# matrix.net
KiCad netlist of a schematic drawn in Altium Designer
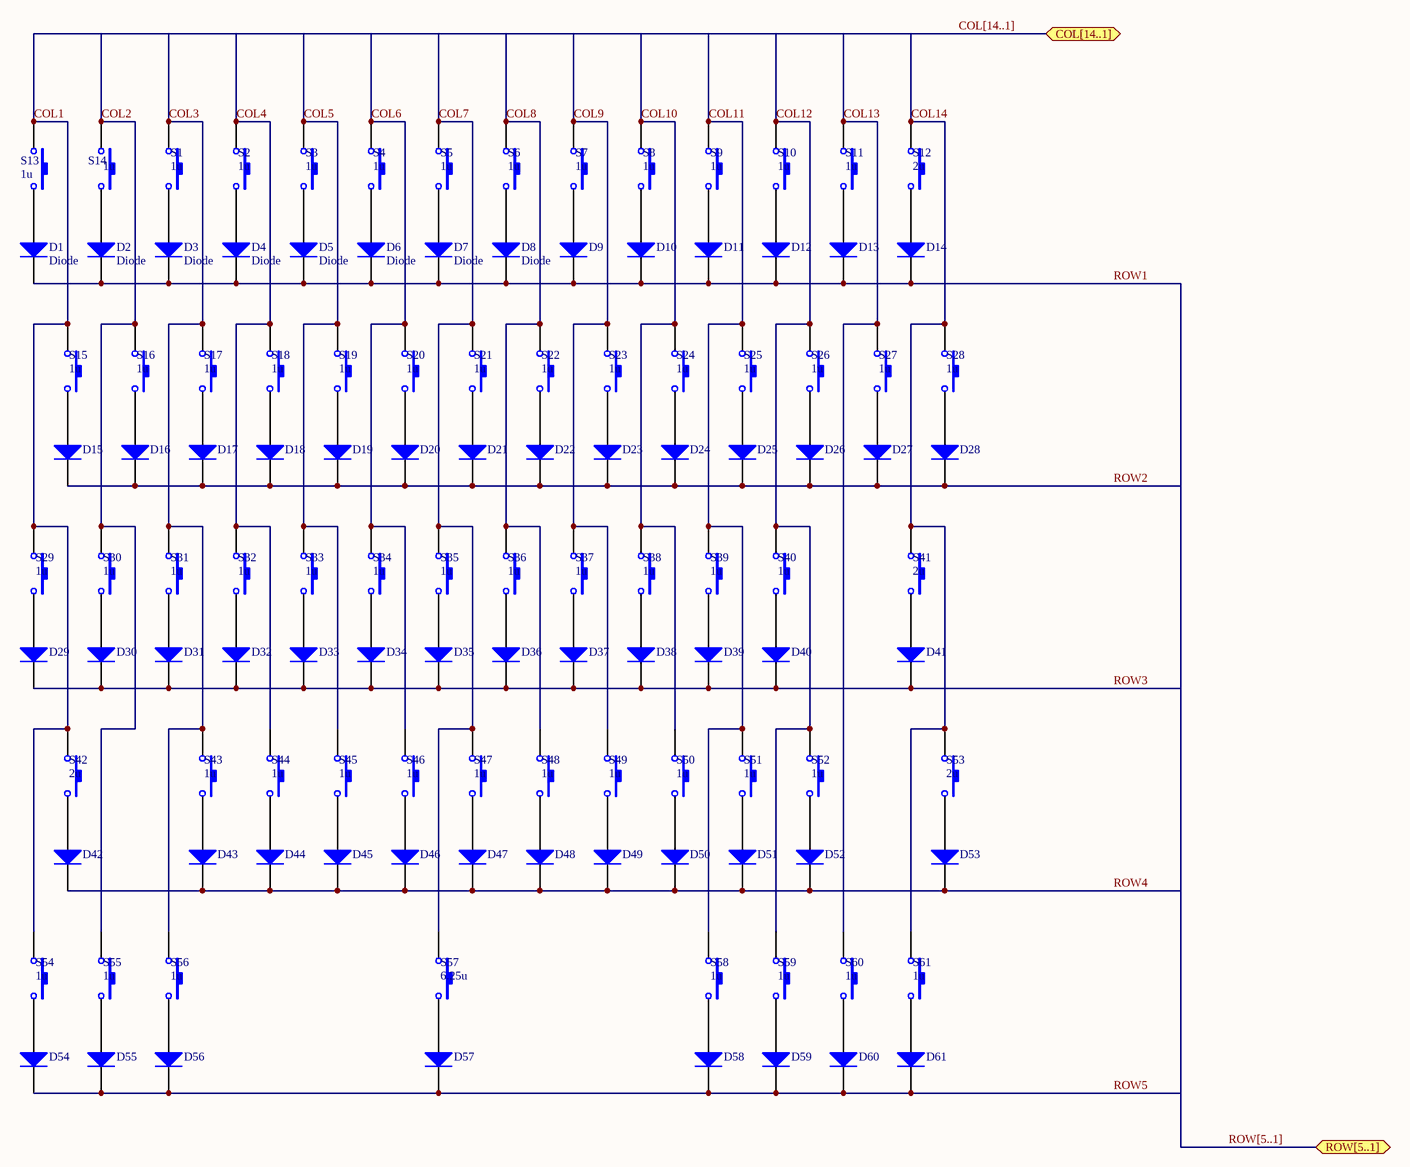
[diagram p0: matrix.SchDoc]

(export (version "E")
  (design (tool "Eeschema 10.0.6"))
  (components
    (comp (ref "D1") (value "Diode") (footprint "SOD-323f") (libsource (lib "MKNZ") (part "Diode")))
    (comp (ref "D2") (value "Diode") (footprint "SOD-323f") (libsource (lib "MKNZ") (part "Diode")))
    (comp (ref "D3") (value "Diode") (footprint "SOD-323f") (libsource (lib "MKNZ") (part "Diode")))
    (comp (ref "D4") (value "Diode") (footprint "SOD-323f") (libsource (lib "MKNZ") (part "Diode")))
    (comp (ref "D5") (value "Diode") (footprint "SOD-323f") (libsource (lib "MKNZ") (part "Diode")))
    (comp (ref "D6") (value "Diode") (footprint "SOD-323f") (libsource (lib "MKNZ") (part "Diode")))
    (comp (ref "D7") (value "Diode") (footprint "SOD-323f") (libsource (lib "MKNZ") (part "Diode")))
    (comp (ref "D8") (value "Diode") (footprint "SOD-323f") (libsource (lib "MKNZ") (part "Diode")))
    (comp (ref "D9") (value "Diode") (footprint "SOD-323f") (libsource (lib "MKNZ") (part "Diode")))
    (comp (ref "D10") (value "Diode") (footprint "SOD-323f") (libsource (lib "MKNZ") (part "Diode")))
    (comp (ref "D11") (value "Diode") (footprint "SOD-323f") (libsource (lib "MKNZ") (part "Diode")))
    (comp (ref "D12") (value "Diode") (footprint "SOD-323f") (libsource (lib "MKNZ") (part "Diode")))
    (comp (ref "D13") (value "Diode") (footprint "SOD-323f") (libsource (lib "MKNZ") (part "Diode")))
    (comp (ref "D14") (value "Diode") (footprint "SOD-323f") (libsource (lib "MKNZ") (part "Diode")))
    (comp (ref "D15") (value "Diode") (footprint "SOD-323f") (libsource (lib "MKNZ") (part "Diode")))
    (comp (ref "D16") (value "Diode") (footprint "SOD-323f") (libsource (lib "MKNZ") (part "Diode")))
    (comp (ref "D17") (value "Diode") (footprint "SOD-323f") (libsource (lib "MKNZ") (part "Diode")))
    (comp (ref "D18") (value "Diode") (footprint "SOD-323f") (libsource (lib "MKNZ") (part "Diode")))
    (comp (ref "D19") (value "Diode") (footprint "SOD-323f") (libsource (lib "MKNZ") (part "Diode")))
    (comp (ref "D20") (value "Diode") (footprint "SOD-323f") (libsource (lib "MKNZ") (part "Diode")))
    (comp (ref "D21") (value "Diode") (footprint "SOD-323f") (libsource (lib "MKNZ") (part "Diode")))
    (comp (ref "D22") (value "Diode") (footprint "SOD-323f") (libsource (lib "MKNZ") (part "Diode")))
    (comp (ref "D23") (value "Diode") (footprint "SOD-323f") (libsource (lib "MKNZ") (part "Diode")))
    (comp (ref "D24") (value "Diode") (footprint "SOD-323f") (libsource (lib "MKNZ") (part "Diode")))
    (comp (ref "D25") (value "Diode") (footprint "SOD-323f") (libsource (lib "MKNZ") (part "Diode")))
    (comp (ref "D26") (value "Diode") (footprint "SOD-323f") (libsource (lib "MKNZ") (part "Diode")))
    (comp (ref "D27") (value "Diode") (footprint "SOD-323f") (libsource (lib "MKNZ") (part "Diode")))
    (comp (ref "D28") (value "Diode") (footprint "SOD-323f") (libsource (lib "MKNZ") (part "Diode")))
    (comp (ref "D29") (value "Diode") (footprint "SOD-323f") (libsource (lib "MKNZ") (part "Diode")))
    (comp (ref "D30") (value "Diode") (footprint "SOD-323f") (libsource (lib "MKNZ") (part "Diode")))
    (comp (ref "D31") (value "Diode") (footprint "SOD-323f") (libsource (lib "MKNZ") (part "Diode")))
    (comp (ref "D32") (value "Diode") (footprint "SOD-323f") (libsource (lib "MKNZ") (part "Diode")))
    (comp (ref "D33") (value "Diode") (footprint "SOD-323f") (libsource (lib "MKNZ") (part "Diode")))
    (comp (ref "D34") (value "Diode") (footprint "SOD-323f") (libsource (lib "MKNZ") (part "Diode")))
    (comp (ref "D35") (value "Diode") (footprint "SOD-323f") (libsource (lib "MKNZ") (part "Diode")))
    (comp (ref "D36") (value "Diode") (footprint "SOD-323f") (libsource (lib "MKNZ") (part "Diode")))
    (comp (ref "D37") (value "Diode") (footprint "SOD-323f") (libsource (lib "MKNZ") (part "Diode")))
    (comp (ref "D38") (value "Diode") (footprint "SOD-323f") (libsource (lib "MKNZ") (part "Diode")))
    (comp (ref "D39") (value "Diode") (footprint "SOD-323f") (libsource (lib "MKNZ") (part "Diode")))
    (comp (ref "D40") (value "Diode") (footprint "SOD-323f") (libsource (lib "MKNZ") (part "Diode")))
    (comp (ref "D41") (value "Diode") (footprint "SOD-323f") (libsource (lib "MKNZ") (part "Diode")))
    (comp (ref "D42") (value "Diode") (footprint "SOD-323f") (libsource (lib "MKNZ") (part "Diode")))
    (comp (ref "D43") (value "Diode") (footprint "SOD-323f") (libsource (lib "MKNZ") (part "Diode")))
    (comp (ref "D44") (value "Diode") (footprint "SOD-323f") (libsource (lib "MKNZ") (part "Diode")))
    (comp (ref "D45") (value "Diode") (footprint "SOD-323f") (libsource (lib "MKNZ") (part "Diode")))
    (comp (ref "D46") (value "Diode") (footprint "SOD-323f") (libsource (lib "MKNZ") (part "Diode")))
    (comp (ref "D47") (value "Diode") (footprint "SOD-323f") (libsource (lib "MKNZ") (part "Diode")))
    (comp (ref "D48") (value "Diode") (footprint "SOD-323f") (libsource (lib "MKNZ") (part "Diode")))
    (comp (ref "D49") (value "Diode") (footprint "SOD-323f") (libsource (lib "MKNZ") (part "Diode")))
    (comp (ref "D50") (value "Diode") (footprint "SOD-323f") (libsource (lib "MKNZ") (part "Diode")))
    (comp (ref "D51") (value "Diode") (footprint "SOD-323f") (libsource (lib "MKNZ") (part "Diode")))
    (comp (ref "D52") (value "Diode") (footprint "SOD-323f") (libsource (lib "MKNZ") (part "Diode")))
    (comp (ref "D53") (value "Diode") (footprint "SOD-323f") (libsource (lib "MKNZ") (part "Diode")))
    (comp (ref "D54") (value "Diode") (footprint "SOD-323f") (libsource (lib "MKNZ") (part "Diode")))
    (comp (ref "D55") (value "Diode") (footprint "SOD-323f") (libsource (lib "MKNZ") (part "Diode")))
    (comp (ref "D56") (value "Diode") (footprint "SOD-323f") (libsource (lib "MKNZ") (part "Diode")))
    (comp (ref "D57") (value "Diode") (footprint "SOD-323f") (libsource (lib "MKNZ") (part "Diode")))
    (comp (ref "D58") (value "Diode") (footprint "SOD-323f") (libsource (lib "MKNZ") (part "Diode")))
    (comp (ref "D59") (value "Diode") (footprint "SOD-323f") (libsource (lib "MKNZ") (part "Diode")))
    (comp (ref "D60") (value "Diode") (footprint "SOD-323f") (libsource (lib "MKNZ") (part "Diode")))
    (comp (ref "D61") (value "Diode") (footprint "SOD-323f") (libsource (lib "MKNZ") (part "Diode")))
    (comp (ref "S1")
      (value "1u")
      (footprint "mx1u")
      (description "1-2u Mx Switch")
      (libsource (lib "MKNZ") (part "1u"))
    )
    (comp (ref "S2")
      (value "1u")
      (footprint "mx1u")
      (description "1-2u Mx Switch")
      (libsource (lib "MKNZ") (part "1u"))
    )
    (comp (ref "S3")
      (value "1u")
      (footprint "mx1u")
      (description "1-2u Mx Switch")
      (libsource (lib "MKNZ") (part "1u"))
    )
    (comp (ref "S4")
      (value "1u")
      (footprint "mx1u")
      (description "1-2u Mx Switch")
      (libsource (lib "MKNZ") (part "1u"))
    )
    (comp (ref "S5")
      (value "1u")
      (footprint "mx1u")
      (description "1-2u Mx Switch")
      (libsource (lib "MKNZ") (part "1u"))
    )
    (comp (ref "S6")
      (value "1u")
      (footprint "mx1u")
      (description "1-2u Mx Switch")
      (libsource (lib "MKNZ") (part "1u"))
    )
    (comp (ref "S7")
      (value "1u")
      (footprint "mx1u")
      (description "1-2u Mx Switch")
      (libsource (lib "MKNZ") (part "1u"))
    )
    (comp (ref "S8")
      (value "1u")
      (footprint "mx1u")
      (description "1-2u Mx Switch")
      (libsource (lib "MKNZ") (part "1u"))
    )
    (comp (ref "S9")
      (value "1u")
      (footprint "mx1u")
      (description "1-2u Mx Switch")
      (libsource (lib "MKNZ") (part "1u"))
    )
    (comp (ref "S10")
      (value "1u")
      (footprint "mx1u")
      (description "1-2u Mx Switch")
      (libsource (lib "MKNZ") (part "1u"))
    )
    (comp (ref "S11")
      (value "1u")
      (footprint "mx1u")
      (description "1-2u Mx Switch")
      (libsource (lib "MKNZ") (part "1u"))
    )
    (comp (ref "S12")
      (value "2u")
      (footprint "mx2u")
      (description "2-3u Mx Switch with pcb mount stabs")
      (libsource (lib "MKNZ") (part "2u"))
    )
    (comp (ref "S13")
      (value "1u")
      (footprint "mx1u")
      (description "1-2u Mx Switch")
      (libsource (lib "MKNZ") (part "1u"))
    )
    (comp (ref "S14")
      (value "1u")
      (footprint "mx1u")
      (description "1-2u Mx Switch")
      (libsource (lib "MKNZ") (part "1u"))
    )
    (comp (ref "S15")
      (value "1u")
      (footprint "mx1u")
      (description "1-2u Mx Switch")
      (libsource (lib "MKNZ") (part "1u"))
    )
    (comp (ref "S16")
      (value "1u")
      (footprint "mx1u")
      (description "1-2u Mx Switch")
      (libsource (lib "MKNZ") (part "1u"))
    )
    (comp (ref "S17")
      (value "1u")
      (footprint "mx1u")
      (description "1-2u Mx Switch")
      (libsource (lib "MKNZ") (part "1u"))
    )
    (comp (ref "S18")
      (value "1u")
      (footprint "mx1u")
      (description "1-2u Mx Switch")
      (libsource (lib "MKNZ") (part "1u"))
    )
    (comp (ref "S19")
      (value "1u")
      (footprint "mx1u")
      (description "1-2u Mx Switch")
      (libsource (lib "MKNZ") (part "1u"))
    )
    (comp (ref "S20")
      (value "1u")
      (footprint "mx1u")
      (description "1-2u Mx Switch")
      (libsource (lib "MKNZ") (part "1u"))
    )
    (comp (ref "S21")
      (value "1u")
      (footprint "mx1u")
      (description "1-2u Mx Switch")
      (libsource (lib "MKNZ") (part "1u"))
    )
    (comp (ref "S22")
      (value "1u")
      (footprint "mx1u")
      (description "1-2u Mx Switch")
      (libsource (lib "MKNZ") (part "1u"))
    )
    (comp (ref "S23")
      (value "1u")
      (footprint "mx1u")
      (description "1-2u Mx Switch")
      (libsource (lib "MKNZ") (part "1u"))
    )
    (comp (ref "S24")
      (value "1u")
      (footprint "mx1u")
      (description "1-2u Mx Switch")
      (libsource (lib "MKNZ") (part "1u"))
    )
    (comp (ref "S25")
      (value "1u")
      (footprint "mx1u")
      (description "1-2u Mx Switch")
      (libsource (lib "MKNZ") (part "1u"))
    )
    (comp (ref "S26")
      (value "1u")
      (footprint "mx1u")
      (description "1-2u Mx Switch")
      (libsource (lib "MKNZ") (part "1u"))
    )
    (comp (ref "S27")
      (value "1u")
      (footprint "mx1u")
      (description "1-2u Mx Switch")
      (libsource (lib "MKNZ") (part "1u"))
    )
    (comp (ref "S28")
      (value "1u")
      (footprint "mx1u")
      (description "1-2u Mx Switch")
      (libsource (lib "MKNZ") (part "1u"))
    )
    (comp (ref "S29")
      (value "1u")
      (footprint "mx1u")
      (description "1-2u Mx Switch")
      (libsource (lib "MKNZ") (part "1u"))
    )
    (comp (ref "S30")
      (value "1u")
      (footprint "mx1u")
      (description "1-2u Mx Switch")
      (libsource (lib "MKNZ") (part "1u"))
    )
    (comp (ref "S31")
      (value "1u")
      (footprint "mx1u")
      (description "1-2u Mx Switch")
      (libsource (lib "MKNZ") (part "1u"))
    )
    (comp (ref "S32")
      (value "1u")
      (footprint "mx1u")
      (description "1-2u Mx Switch")
      (libsource (lib "MKNZ") (part "1u"))
    )
    (comp (ref "S33")
      (value "1u")
      (footprint "mx1u")
      (description "1-2u Mx Switch")
      (libsource (lib "MKNZ") (part "1u"))
    )
    (comp (ref "S34")
      (value "1u")
      (footprint "mx1u")
      (description "1-2u Mx Switch")
      (libsource (lib "MKNZ") (part "1u"))
    )
    (comp (ref "S35")
      (value "1u")
      (footprint "mx1u")
      (description "1-2u Mx Switch")
      (libsource (lib "MKNZ") (part "1u"))
    )
    (comp (ref "S36")
      (value "1u")
      (footprint "mx1u")
      (description "1-2u Mx Switch")
      (libsource (lib "MKNZ") (part "1u"))
    )
    (comp (ref "S37")
      (value "1u")
      (footprint "mx1u")
      (description "1-2u Mx Switch")
      (libsource (lib "MKNZ") (part "1u"))
    )
    (comp (ref "S38")
      (value "1u")
      (footprint "mx1u")
      (description "1-2u Mx Switch")
      (libsource (lib "MKNZ") (part "1u"))
    )
    (comp (ref "S39")
      (value "1u")
      (footprint "mx1u")
      (description "1-2u Mx Switch")
      (libsource (lib "MKNZ") (part "1u"))
    )
    (comp (ref "S40")
      (value "1u")
      (footprint "mx1u")
      (description "1-2u Mx Switch")
      (libsource (lib "MKNZ") (part "1u"))
    )
    (comp (ref "S41")
      (value "2u")
      (footprint "mx2u")
      (description "2-3u Mx Switch with pcb mount stabs")
      (libsource (lib "MKNZ") (part "2u"))
    )
    (comp (ref "S42")
      (value "2u")
      (footprint "mx2u")
      (description "2-3u Mx Switch with pcb mount stabs")
      (libsource (lib "MKNZ") (part "2u"))
    )
    (comp (ref "S43")
      (value "1u")
      (footprint "mx1u")
      (description "1-2u Mx Switch")
      (libsource (lib "MKNZ") (part "1u"))
    )
    (comp (ref "S44")
      (value "1u")
      (footprint "mx1u")
      (description "1-2u Mx Switch")
      (libsource (lib "MKNZ") (part "1u"))
    )
    (comp (ref "S45")
      (value "1u")
      (footprint "mx1u")
      (description "1-2u Mx Switch")
      (libsource (lib "MKNZ") (part "1u"))
    )
    (comp (ref "S46")
      (value "1u")
      (footprint "mx1u")
      (description "1-2u Mx Switch")
      (libsource (lib "MKNZ") (part "1u"))
    )
    (comp (ref "S47")
      (value "1u")
      (footprint "mx1u")
      (description "1-2u Mx Switch")
      (libsource (lib "MKNZ") (part "1u"))
    )
    (comp (ref "S48")
      (value "1u")
      (footprint "mx1u")
      (description "1-2u Mx Switch")
      (libsource (lib "MKNZ") (part "1u"))
    )
    (comp (ref "S49")
      (value "1u")
      (footprint "mx1u")
      (description "1-2u Mx Switch")
      (libsource (lib "MKNZ") (part "1u"))
    )
    (comp (ref "S50")
      (value "1u")
      (footprint "mx1u")
      (description "1-2u Mx Switch")
      (libsource (lib "MKNZ") (part "1u"))
    )
    (comp (ref "S51")
      (value "1u")
      (footprint "mx1u")
      (description "1-2u Mx Switch")
      (libsource (lib "MKNZ") (part "1u"))
    )
    (comp (ref "S52")
      (value "1u")
      (footprint "mx1u")
      (description "1-2u Mx Switch")
      (libsource (lib "MKNZ") (part "1u"))
    )
    (comp (ref "S53")
      (value "2u")
      (footprint "mx2u")
      (description "2-3u Mx Switch with pcb mount stabs")
      (libsource (lib "MKNZ") (part "2u"))
    )
    (comp (ref "S54")
      (value "1u")
      (footprint "mx1u")
      (description "1-2u Mx Switch")
      (libsource (lib "MKNZ") (part "1u"))
    )
    (comp (ref "S55")
      (value "1u")
      (footprint "mx1u")
      (description "1-2u Mx Switch")
      (libsource (lib "MKNZ") (part "1u"))
    )
    (comp (ref "S56")
      (value "1u")
      (footprint "mx1u")
      (description "1-2u Mx Switch")
      (libsource (lib "MKNZ") (part "1u"))
    )
    (comp (ref "S57")
      (value "6.25u")
      (footprint "mx6.25u flipped stab")
      (description "6.25u Mx Switch with pcb mount stabs")
      (libsource (lib "MKNZ") (part "6.25u"))
    )
    (comp (ref "S58")
      (value "1u")
      (footprint "mx1u")
      (description "1-2u Mx Switch")
      (libsource (lib "MKNZ") (part "1u"))
    )
    (comp (ref "S59")
      (value "1u")
      (footprint "mx1u")
      (description "1-2u Mx Switch")
      (libsource (lib "MKNZ") (part "1u"))
    )
    (comp (ref "S60")
      (value "1u")
      (footprint "mx1u")
      (description "1-2u Mx Switch")
      (libsource (lib "MKNZ") (part "1u"))
    )
    (comp (ref "S61")
      (value "1u")
      (footprint "mx1u")
      (description "1-2u Mx Switch")
      (libsource (lib "MKNZ") (part "1u"))
    )
  )
  (nets
    (net (code "1") (name "/COL1") (class "Default")
      (node (ref "S13") (pin "1") (pinfunction "1_1") (pintype "passive"))
      (node (ref "S15") (pin "1") (pinfunction "1_1") (pintype "passive"))
      (node (ref "S29") (pin "1") (pinfunction "1_1") (pintype "passive"))
      (node (ref "S42") (pin "1") (pinfunction "1_1") (pintype "passive"))
      (node (ref "S54") (pin "1") (pinfunction "1_1") (pintype "passive"))
    )
    (net (code "2") (name "/COL2") (class "Default")
      (node (ref "S14") (pin "1") (pinfunction "1_1") (pintype "passive"))
      (node (ref "S16") (pin "1") (pinfunction "1_1") (pintype "passive"))
      (node (ref "S30") (pin "1") (pinfunction "1_1") (pintype "passive"))
      (node (ref "S55") (pin "1") (pinfunction "1_1") (pintype "passive"))
    )
    (net (code "3") (name "/COL3") (class "Default")
      (node (ref "S1") (pin "1") (pinfunction "1_1") (pintype "passive"))
      (node (ref "S17") (pin "1") (pinfunction "1_1") (pintype "passive"))
      (node (ref "S31") (pin "1") (pinfunction "1_1") (pintype "passive"))
      (node (ref "S43") (pin "1") (pinfunction "1_1") (pintype "passive"))
      (node (ref "S56") (pin "1") (pinfunction "1_1") (pintype "passive"))
    )
    (net (code "4") (name "/COL4") (class "Default")
      (node (ref "S18") (pin "1") (pinfunction "1_1") (pintype "passive"))
      (node (ref "S2") (pin "1") (pinfunction "1_1") (pintype "passive"))
      (node (ref "S32") (pin "1") (pinfunction "1_1") (pintype "passive"))
      (node (ref "S44") (pin "1") (pinfunction "1_1") (pintype "passive"))
    )
    (net (code "5") (name "/COL5") (class "Default")
      (node (ref "S19") (pin "1") (pinfunction "1_1") (pintype "passive"))
      (node (ref "S3") (pin "1") (pinfunction "1_1") (pintype "passive"))
      (node (ref "S33") (pin "1") (pinfunction "1_1") (pintype "passive"))
      (node (ref "S45") (pin "1") (pinfunction "1_1") (pintype "passive"))
    )
    (net (code "6") (name "/COL6") (class "Default")
      (node (ref "S20") (pin "1") (pinfunction "1_1") (pintype "passive"))
      (node (ref "S34") (pin "1") (pinfunction "1_1") (pintype "passive"))
      (node (ref "S4") (pin "1") (pinfunction "1_1") (pintype "passive"))
      (node (ref "S46") (pin "1") (pinfunction "1_1") (pintype "passive"))
    )
    (net (code "7") (name "/COL7") (class "Default")
      (node (ref "S21") (pin "1") (pinfunction "1_1") (pintype "passive"))
      (node (ref "S35") (pin "1") (pinfunction "1_1") (pintype "passive"))
      (node (ref "S47") (pin "1") (pinfunction "1_1") (pintype "passive"))
      (node (ref "S5") (pin "1") (pinfunction "1_1") (pintype "passive"))
      (node (ref "S57") (pin "1") (pinfunction "1_1") (pintype "passive"))
    )
    (net (code "8") (name "/COL8") (class "Default")
      (node (ref "S22") (pin "1") (pinfunction "1_1") (pintype "passive"))
      (node (ref "S36") (pin "1") (pinfunction "1_1") (pintype "passive"))
      (node (ref "S48") (pin "1") (pinfunction "1_1") (pintype "passive"))
      (node (ref "S6") (pin "1") (pinfunction "1_1") (pintype "passive"))
    )
    (net (code "9") (name "/COL9") (class "Default")
      (node (ref "S23") (pin "1") (pinfunction "1_1") (pintype "passive"))
      (node (ref "S37") (pin "1") (pinfunction "1_1") (pintype "passive"))
      (node (ref "S49") (pin "1") (pinfunction "1_1") (pintype "passive"))
      (node (ref "S7") (pin "1") (pinfunction "1_1") (pintype "passive"))
    )
    (net (code "10") (name "/COL10") (class "Default")
      (node (ref "S24") (pin "1") (pinfunction "1_1") (pintype "passive"))
      (node (ref "S38") (pin "1") (pinfunction "1_1") (pintype "passive"))
      (node (ref "S50") (pin "1") (pinfunction "1_1") (pintype "passive"))
      (node (ref "S8") (pin "1") (pinfunction "1_1") (pintype "passive"))
    )
    (net (code "11") (name "/COL11") (class "Default")
      (node (ref "S25") (pin "1") (pinfunction "1_1") (pintype "passive"))
      (node (ref "S39") (pin "1") (pinfunction "1_1") (pintype "passive"))
      (node (ref "S51") (pin "1") (pinfunction "1_1") (pintype "passive"))
      (node (ref "S58") (pin "1") (pinfunction "1_1") (pintype "passive"))
      (node (ref "S9") (pin "1") (pinfunction "1_1") (pintype "passive"))
    )
    (net (code "12") (name "/COL12") (class "Default")
      (node (ref "S10") (pin "1") (pinfunction "1_1") (pintype "passive"))
      (node (ref "S26") (pin "1") (pinfunction "1_1") (pintype "passive"))
      (node (ref "S40") (pin "1") (pinfunction "1_1") (pintype "passive"))
      (node (ref "S52") (pin "1") (pinfunction "1_1") (pintype "passive"))
      (node (ref "S59") (pin "1") (pinfunction "1_1") (pintype "passive"))
    )
    (net (code "13") (name "/COL13") (class "Default")
      (node (ref "S11") (pin "1") (pinfunction "1_1") (pintype "passive"))
      (node (ref "S27") (pin "1") (pinfunction "1_1") (pintype "passive"))
      (node (ref "S60") (pin "1") (pinfunction "1_1") (pintype "passive"))
    )
    (net (code "14") (name "/COL14") (class "Default")
      (node (ref "S12") (pin "1") (pinfunction "1_1") (pintype "passive"))
      (node (ref "S28") (pin "1") (pinfunction "1_1") (pintype "passive"))
      (node (ref "S41") (pin "1") (pinfunction "1_1") (pintype "passive"))
      (node (ref "S53") (pin "1") (pinfunction "1_1") (pintype "passive"))
      (node (ref "S61") (pin "1") (pinfunction "1_1") (pintype "passive"))
    )
    (net (code "16") (name "/ROW1") (class "Default")
      (node (ref "D1") (pin "1") (pinfunction "K_1") (pintype "passive"))
      (node (ref "D10") (pin "1") (pinfunction "K_1") (pintype "passive"))
      (node (ref "D11") (pin "1") (pinfunction "K_1") (pintype "passive"))
      (node (ref "D12") (pin "1") (pinfunction "K_1") (pintype "passive"))
      (node (ref "D13") (pin "1") (pinfunction "K_1") (pintype "passive"))
      (node (ref "D14") (pin "1") (pinfunction "K_1") (pintype "passive"))
      (node (ref "D2") (pin "1") (pinfunction "K_1") (pintype "passive"))
      (node (ref "D3") (pin "1") (pinfunction "K_1") (pintype "passive"))
      (node (ref "D4") (pin "1") (pinfunction "K_1") (pintype "passive"))
      (node (ref "D5") (pin "1") (pinfunction "K_1") (pintype "passive"))
      (node (ref "D6") (pin "1") (pinfunction "K_1") (pintype "passive"))
      (node (ref "D7") (pin "1") (pinfunction "K_1") (pintype "passive"))
      (node (ref "D8") (pin "1") (pinfunction "K_1") (pintype "passive"))
      (node (ref "D9") (pin "1") (pinfunction "K_1") (pintype "passive"))
    )
    (net (code "17") (name "/ROW2") (class "Default")
      (node (ref "D15") (pin "1") (pinfunction "K_1") (pintype "passive"))
      (node (ref "D16") (pin "1") (pinfunction "K_1") (pintype "passive"))
      (node (ref "D17") (pin "1") (pinfunction "K_1") (pintype "passive"))
      (node (ref "D18") (pin "1") (pinfunction "K_1") (pintype "passive"))
      (node (ref "D19") (pin "1") (pinfunction "K_1") (pintype "passive"))
      (node (ref "D20") (pin "1") (pinfunction "K_1") (pintype "passive"))
      (node (ref "D21") (pin "1") (pinfunction "K_1") (pintype "passive"))
      (node (ref "D22") (pin "1") (pinfunction "K_1") (pintype "passive"))
      (node (ref "D23") (pin "1") (pinfunction "K_1") (pintype "passive"))
      (node (ref "D24") (pin "1") (pinfunction "K_1") (pintype "passive"))
      (node (ref "D25") (pin "1") (pinfunction "K_1") (pintype "passive"))
      (node (ref "D26") (pin "1") (pinfunction "K_1") (pintype "passive"))
      (node (ref "D27") (pin "1") (pinfunction "K_1") (pintype "passive"))
      (node (ref "D28") (pin "1") (pinfunction "K_1") (pintype "passive"))
    )
    (net (code "18") (name "/ROW3") (class "Default")
      (node (ref "D29") (pin "1") (pinfunction "K_1") (pintype "passive"))
      (node (ref "D30") (pin "1") (pinfunction "K_1") (pintype "passive"))
      (node (ref "D31") (pin "1") (pinfunction "K_1") (pintype "passive"))
      (node (ref "D32") (pin "1") (pinfunction "K_1") (pintype "passive"))
      (node (ref "D33") (pin "1") (pinfunction "K_1") (pintype "passive"))
      (node (ref "D34") (pin "1") (pinfunction "K_1") (pintype "passive"))
      (node (ref "D35") (pin "1") (pinfunction "K_1") (pintype "passive"))
      (node (ref "D36") (pin "1") (pinfunction "K_1") (pintype "passive"))
      (node (ref "D37") (pin "1") (pinfunction "K_1") (pintype "passive"))
      (node (ref "D38") (pin "1") (pinfunction "K_1") (pintype "passive"))
      (node (ref "D39") (pin "1") (pinfunction "K_1") (pintype "passive"))
      (node (ref "D40") (pin "1") (pinfunction "K_1") (pintype "passive"))
      (node (ref "D41") (pin "1") (pinfunction "K_1") (pintype "passive"))
    )
    (net (code "19") (name "/ROW4") (class "Default")
      (node (ref "D42") (pin "1") (pinfunction "K_1") (pintype "passive"))
      (node (ref "D43") (pin "1") (pinfunction "K_1") (pintype "passive"))
      (node (ref "D44") (pin "1") (pinfunction "K_1") (pintype "passive"))
      (node (ref "D45") (pin "1") (pinfunction "K_1") (pintype "passive"))
      (node (ref "D46") (pin "1") (pinfunction "K_1") (pintype "passive"))
      (node (ref "D47") (pin "1") (pinfunction "K_1") (pintype "passive"))
      (node (ref "D48") (pin "1") (pinfunction "K_1") (pintype "passive"))
      (node (ref "D49") (pin "1") (pinfunction "K_1") (pintype "passive"))
      (node (ref "D50") (pin "1") (pinfunction "K_1") (pintype "passive"))
      (node (ref "D51") (pin "1") (pinfunction "K_1") (pintype "passive"))
      (node (ref "D52") (pin "1") (pinfunction "K_1") (pintype "passive"))
      (node (ref "D53") (pin "1") (pinfunction "K_1") (pintype "passive"))
    )
    (net (code "20") (name "/ROW5") (class "Default")
      (node (ref "D54") (pin "1") (pinfunction "K_1") (pintype "passive"))
      (node (ref "D55") (pin "1") (pinfunction "K_1") (pintype "passive"))
      (node (ref "D56") (pin "1") (pinfunction "K_1") (pintype "passive"))
      (node (ref "D57") (pin "1") (pinfunction "K_1") (pintype "passive"))
      (node (ref "D58") (pin "1") (pinfunction "K_1") (pintype "passive"))
      (node (ref "D59") (pin "1") (pinfunction "K_1") (pintype "passive"))
      (node (ref "D60") (pin "1") (pinfunction "K_1") (pintype "passive"))
      (node (ref "D61") (pin "1") (pinfunction "K_1") (pintype "passive"))
    )
    (net (code "22") (name "Net-(D1-A)") (class "Default")
      (node (ref "D1") (pin "2") (pinfunction "A_2") (pintype "passive"))
      (node (ref "S13") (pin "2") (pinfunction "2_2") (pintype "passive"))
    )
    (net (code "23") (name "Net-(D2-A)") (class "Default")
      (node (ref "D2") (pin "2") (pinfunction "A_2") (pintype "passive"))
      (node (ref "S14") (pin "2") (pinfunction "2_2") (pintype "passive"))
    )
    (net (code "24") (name "Net-(D3-A)") (class "Default")
      (node (ref "D3") (pin "2") (pinfunction "A_2") (pintype "passive"))
      (node (ref "S1") (pin "2") (pinfunction "2_2") (pintype "passive"))
    )
    (net (code "25") (name "Net-(D4-A)") (class "Default")
      (node (ref "D4") (pin "2") (pinfunction "A_2") (pintype "passive"))
      (node (ref "S2") (pin "2") (pinfunction "2_2") (pintype "passive"))
    )
    (net (code "26") (name "Net-(D5-A)") (class "Default")
      (node (ref "D5") (pin "2") (pinfunction "A_2") (pintype "passive"))
      (node (ref "S3") (pin "2") (pinfunction "2_2") (pintype "passive"))
    )
    (net (code "27") (name "Net-(D6-A)") (class "Default")
      (node (ref "D6") (pin "2") (pinfunction "A_2") (pintype "passive"))
      (node (ref "S4") (pin "2") (pinfunction "2_2") (pintype "passive"))
    )
    (net (code "28") (name "Net-(D7-A)") (class "Default")
      (node (ref "D7") (pin "2") (pinfunction "A_2") (pintype "passive"))
      (node (ref "S5") (pin "2") (pinfunction "2_2") (pintype "passive"))
    )
    (net (code "29") (name "Net-(D8-A)") (class "Default")
      (node (ref "D8") (pin "2") (pinfunction "A_2") (pintype "passive"))
      (node (ref "S6") (pin "2") (pinfunction "2_2") (pintype "passive"))
    )
    (net (code "30") (name "Net-(D9-A)") (class "Default")
      (node (ref "D9") (pin "2") (pinfunction "A_2") (pintype "passive"))
      (node (ref "S7") (pin "2") (pinfunction "2_2") (pintype "passive"))
    )
    (net (code "31") (name "Net-(D10-A)") (class "Default")
      (node (ref "D10") (pin "2") (pinfunction "A_2") (pintype "passive"))
      (node (ref "S8") (pin "2") (pinfunction "2_2") (pintype "passive"))
    )
    (net (code "32") (name "Net-(D11-A)") (class "Default")
      (node (ref "D11") (pin "2") (pinfunction "A_2") (pintype "passive"))
      (node (ref "S9") (pin "2") (pinfunction "2_2") (pintype "passive"))
    )
    (net (code "33") (name "Net-(D12-A)") (class "Default")
      (node (ref "D12") (pin "2") (pinfunction "A_2") (pintype "passive"))
      (node (ref "S10") (pin "2") (pinfunction "2_2") (pintype "passive"))
    )
    (net (code "34") (name "Net-(D13-A)") (class "Default")
      (node (ref "D13") (pin "2") (pinfunction "A_2") (pintype "passive"))
      (node (ref "S11") (pin "2") (pinfunction "2_2") (pintype "passive"))
    )
    (net (code "35") (name "Net-(D14-A)") (class "Default")
      (node (ref "D14") (pin "2") (pinfunction "A_2") (pintype "passive"))
      (node (ref "S12") (pin "2") (pinfunction "2_2") (pintype "passive"))
    )
    (net (code "36") (name "Net-(D15-A)") (class "Default")
      (node (ref "D15") (pin "2") (pinfunction "A_2") (pintype "passive"))
      (node (ref "S15") (pin "2") (pinfunction "2_2") (pintype "passive"))
    )
    (net (code "37") (name "Net-(D16-A)") (class "Default")
      (node (ref "D16") (pin "2") (pinfunction "A_2") (pintype "passive"))
      (node (ref "S16") (pin "2") (pinfunction "2_2") (pintype "passive"))
    )
    (net (code "38") (name "Net-(D17-A)") (class "Default")
      (node (ref "D17") (pin "2") (pinfunction "A_2") (pintype "passive"))
      (node (ref "S17") (pin "2") (pinfunction "2_2") (pintype "passive"))
    )
    (net (code "39") (name "Net-(D18-A)") (class "Default")
      (node (ref "D18") (pin "2") (pinfunction "A_2") (pintype "passive"))
      (node (ref "S18") (pin "2") (pinfunction "2_2") (pintype "passive"))
    )
    (net (code "40") (name "Net-(D19-A)") (class "Default")
      (node (ref "D19") (pin "2") (pinfunction "A_2") (pintype "passive"))
      (node (ref "S19") (pin "2") (pinfunction "2_2") (pintype "passive"))
    )
    (net (code "41") (name "Net-(D20-A)") (class "Default")
      (node (ref "D20") (pin "2") (pinfunction "A_2") (pintype "passive"))
      (node (ref "S20") (pin "2") (pinfunction "2_2") (pintype "passive"))
    )
    (net (code "42") (name "Net-(D21-A)") (class "Default")
      (node (ref "D21") (pin "2") (pinfunction "A_2") (pintype "passive"))
      (node (ref "S21") (pin "2") (pinfunction "2_2") (pintype "passive"))
    )
    (net (code "43") (name "Net-(D22-A)") (class "Default")
      (node (ref "D22") (pin "2") (pinfunction "A_2") (pintype "passive"))
      (node (ref "S22") (pin "2") (pinfunction "2_2") (pintype "passive"))
    )
    (net (code "44") (name "Net-(D23-A)") (class "Default")
      (node (ref "D23") (pin "2") (pinfunction "A_2") (pintype "passive"))
      (node (ref "S23") (pin "2") (pinfunction "2_2") (pintype "passive"))
    )
    (net (code "45") (name "Net-(D24-A)") (class "Default")
      (node (ref "D24") (pin "2") (pinfunction "A_2") (pintype "passive"))
      (node (ref "S24") (pin "2") (pinfunction "2_2") (pintype "passive"))
    )
    (net (code "46") (name "Net-(D25-A)") (class "Default")
      (node (ref "D25") (pin "2") (pinfunction "A_2") (pintype "passive"))
      (node (ref "S25") (pin "2") (pinfunction "2_2") (pintype "passive"))
    )
    (net (code "47") (name "Net-(D26-A)") (class "Default")
      (node (ref "D26") (pin "2") (pinfunction "A_2") (pintype "passive"))
      (node (ref "S26") (pin "2") (pinfunction "2_2") (pintype "passive"))
    )
    (net (code "48") (name "Net-(D27-A)") (class "Default")
      (node (ref "D27") (pin "2") (pinfunction "A_2") (pintype "passive"))
      (node (ref "S27") (pin "2") (pinfunction "2_2") (pintype "passive"))
    )
    (net (code "49") (name "Net-(D28-A)") (class "Default")
      (node (ref "D28") (pin "2") (pinfunction "A_2") (pintype "passive"))
      (node (ref "S28") (pin "2") (pinfunction "2_2") (pintype "passive"))
    )
    (net (code "50") (name "Net-(D29-A)") (class "Default")
      (node (ref "D29") (pin "2") (pinfunction "A_2") (pintype "passive"))
      (node (ref "S29") (pin "2") (pinfunction "2_2") (pintype "passive"))
    )
    (net (code "51") (name "Net-(D30-A)") (class "Default")
      (node (ref "D30") (pin "2") (pinfunction "A_2") (pintype "passive"))
      (node (ref "S30") (pin "2") (pinfunction "2_2") (pintype "passive"))
    )
    (net (code "52") (name "Net-(D31-A)") (class "Default")
      (node (ref "D31") (pin "2") (pinfunction "A_2") (pintype "passive"))
      (node (ref "S31") (pin "2") (pinfunction "2_2") (pintype "passive"))
    )
    (net (code "53") (name "Net-(D32-A)") (class "Default")
      (node (ref "D32") (pin "2") (pinfunction "A_2") (pintype "passive"))
      (node (ref "S32") (pin "2") (pinfunction "2_2") (pintype "passive"))
    )
    (net (code "54") (name "Net-(D33-A)") (class "Default")
      (node (ref "D33") (pin "2") (pinfunction "A_2") (pintype "passive"))
      (node (ref "S33") (pin "2") (pinfunction "2_2") (pintype "passive"))
    )
    (net (code "55") (name "Net-(D34-A)") (class "Default")
      (node (ref "D34") (pin "2") (pinfunction "A_2") (pintype "passive"))
      (node (ref "S34") (pin "2") (pinfunction "2_2") (pintype "passive"))
    )
    (net (code "56") (name "Net-(D35-A)") (class "Default")
      (node (ref "D35") (pin "2") (pinfunction "A_2") (pintype "passive"))
      (node (ref "S35") (pin "2") (pinfunction "2_2") (pintype "passive"))
    )
    (net (code "57") (name "Net-(D36-A)") (class "Default")
      (node (ref "D36") (pin "2") (pinfunction "A_2") (pintype "passive"))
      (node (ref "S36") (pin "2") (pinfunction "2_2") (pintype "passive"))
    )
    (net (code "58") (name "Net-(D37-A)") (class "Default")
      (node (ref "D37") (pin "2") (pinfunction "A_2") (pintype "passive"))
      (node (ref "S37") (pin "2") (pinfunction "2_2") (pintype "passive"))
    )
    (net (code "59") (name "Net-(D38-A)") (class "Default")
      (node (ref "D38") (pin "2") (pinfunction "A_2") (pintype "passive"))
      (node (ref "S38") (pin "2") (pinfunction "2_2") (pintype "passive"))
    )
    (net (code "60") (name "Net-(D39-A)") (class "Default")
      (node (ref "D39") (pin "2") (pinfunction "A_2") (pintype "passive"))
      (node (ref "S39") (pin "2") (pinfunction "2_2") (pintype "passive"))
    )
    (net (code "61") (name "Net-(D40-A)") (class "Default")
      (node (ref "D40") (pin "2") (pinfunction "A_2") (pintype "passive"))
      (node (ref "S40") (pin "2") (pinfunction "2_2") (pintype "passive"))
    )
    (net (code "62") (name "Net-(D41-A)") (class "Default")
      (node (ref "D41") (pin "2") (pinfunction "A_2") (pintype "passive"))
      (node (ref "S41") (pin "2") (pinfunction "2_2") (pintype "passive"))
    )
    (net (code "63") (name "Net-(D42-A)") (class "Default")
      (node (ref "D42") (pin "2") (pinfunction "A_2") (pintype "passive"))
      (node (ref "S42") (pin "2") (pinfunction "2_2") (pintype "passive"))
    )
    (net (code "64") (name "Net-(D43-A)") (class "Default")
      (node (ref "D43") (pin "2") (pinfunction "A_2") (pintype "passive"))
      (node (ref "S43") (pin "2") (pinfunction "2_2") (pintype "passive"))
    )
    (net (code "65") (name "Net-(D44-A)") (class "Default")
      (node (ref "D44") (pin "2") (pinfunction "A_2") (pintype "passive"))
      (node (ref "S44") (pin "2") (pinfunction "2_2") (pintype "passive"))
    )
    (net (code "66") (name "Net-(D45-A)") (class "Default")
      (node (ref "D45") (pin "2") (pinfunction "A_2") (pintype "passive"))
      (node (ref "S45") (pin "2") (pinfunction "2_2") (pintype "passive"))
    )
    (net (code "67") (name "Net-(D46-A)") (class "Default")
      (node (ref "D46") (pin "2") (pinfunction "A_2") (pintype "passive"))
      (node (ref "S46") (pin "2") (pinfunction "2_2") (pintype "passive"))
    )
    (net (code "68") (name "Net-(D47-A)") (class "Default")
      (node (ref "D47") (pin "2") (pinfunction "A_2") (pintype "passive"))
      (node (ref "S47") (pin "2") (pinfunction "2_2") (pintype "passive"))
    )
    (net (code "69") (name "Net-(D48-A)") (class "Default")
      (node (ref "D48") (pin "2") (pinfunction "A_2") (pintype "passive"))
      (node (ref "S48") (pin "2") (pinfunction "2_2") (pintype "passive"))
    )
    (net (code "70") (name "Net-(D49-A)") (class "Default")
      (node (ref "D49") (pin "2") (pinfunction "A_2") (pintype "passive"))
      (node (ref "S49") (pin "2") (pinfunction "2_2") (pintype "passive"))
    )
    (net (code "71") (name "Net-(D50-A)") (class "Default")
      (node (ref "D50") (pin "2") (pinfunction "A_2") (pintype "passive"))
      (node (ref "S50") (pin "2") (pinfunction "2_2") (pintype "passive"))
    )
    (net (code "72") (name "Net-(D51-A)") (class "Default")
      (node (ref "D51") (pin "2") (pinfunction "A_2") (pintype "passive"))
      (node (ref "S51") (pin "2") (pinfunction "2_2") (pintype "passive"))
    )
    (net (code "73") (name "Net-(D52-A)") (class "Default")
      (node (ref "D52") (pin "2") (pinfunction "A_2") (pintype "passive"))
      (node (ref "S52") (pin "2") (pinfunction "2_2") (pintype "passive"))
    )
    (net (code "74") (name "Net-(D53-A)") (class "Default")
      (node (ref "D53") (pin "2") (pinfunction "A_2") (pintype "passive"))
      (node (ref "S53") (pin "2") (pinfunction "2_2") (pintype "passive"))
    )
    (net (code "75") (name "Net-(D54-A)") (class "Default")
      (node (ref "D54") (pin "2") (pinfunction "A_2") (pintype "passive"))
      (node (ref "S54") (pin "2") (pinfunction "2_2") (pintype "passive"))
    )
    (net (code "76") (name "Net-(D55-A)") (class "Default")
      (node (ref "D55") (pin "2") (pinfunction "A_2") (pintype "passive"))
      (node (ref "S55") (pin "2") (pinfunction "2_2") (pintype "passive"))
    )
    (net (code "77") (name "Net-(D56-A)") (class "Default")
      (node (ref "D56") (pin "2") (pinfunction "A_2") (pintype "passive"))
      (node (ref "S56") (pin "2") (pinfunction "2_2") (pintype "passive"))
    )
    (net (code "78") (name "Net-(D57-A)") (class "Default")
      (node (ref "D57") (pin "2") (pinfunction "A_2") (pintype "passive"))
      (node (ref "S57") (pin "2") (pinfunction "2_2") (pintype "passive"))
    )
    (net (code "79") (name "Net-(D58-A)") (class "Default")
      (node (ref "D58") (pin "2") (pinfunction "A_2") (pintype "passive"))
      (node (ref "S58") (pin "2") (pinfunction "2_2") (pintype "passive"))
    )
    (net (code "80") (name "Net-(D59-A)") (class "Default")
      (node (ref "D59") (pin "2") (pinfunction "A_2") (pintype "passive"))
      (node (ref "S59") (pin "2") (pinfunction "2_2") (pintype "passive"))
    )
    (net (code "81") (name "Net-(D60-A)") (class "Default")
      (node (ref "D60") (pin "2") (pinfunction "A_2") (pintype "passive"))
      (node (ref "S60") (pin "2") (pinfunction "2_2") (pintype "passive"))
    )
    (net (code "82") (name "Net-(D61-A)") (class "Default")
      (node (ref "D61") (pin "2") (pinfunction "A_2") (pintype "passive"))
      (node (ref "S61") (pin "2") (pinfunction "2_2") (pintype "passive"))
    )
  )
)
